# SHIELD_PICO_PTH.net
KiCad netlist of a schematic drawn in EAGLE
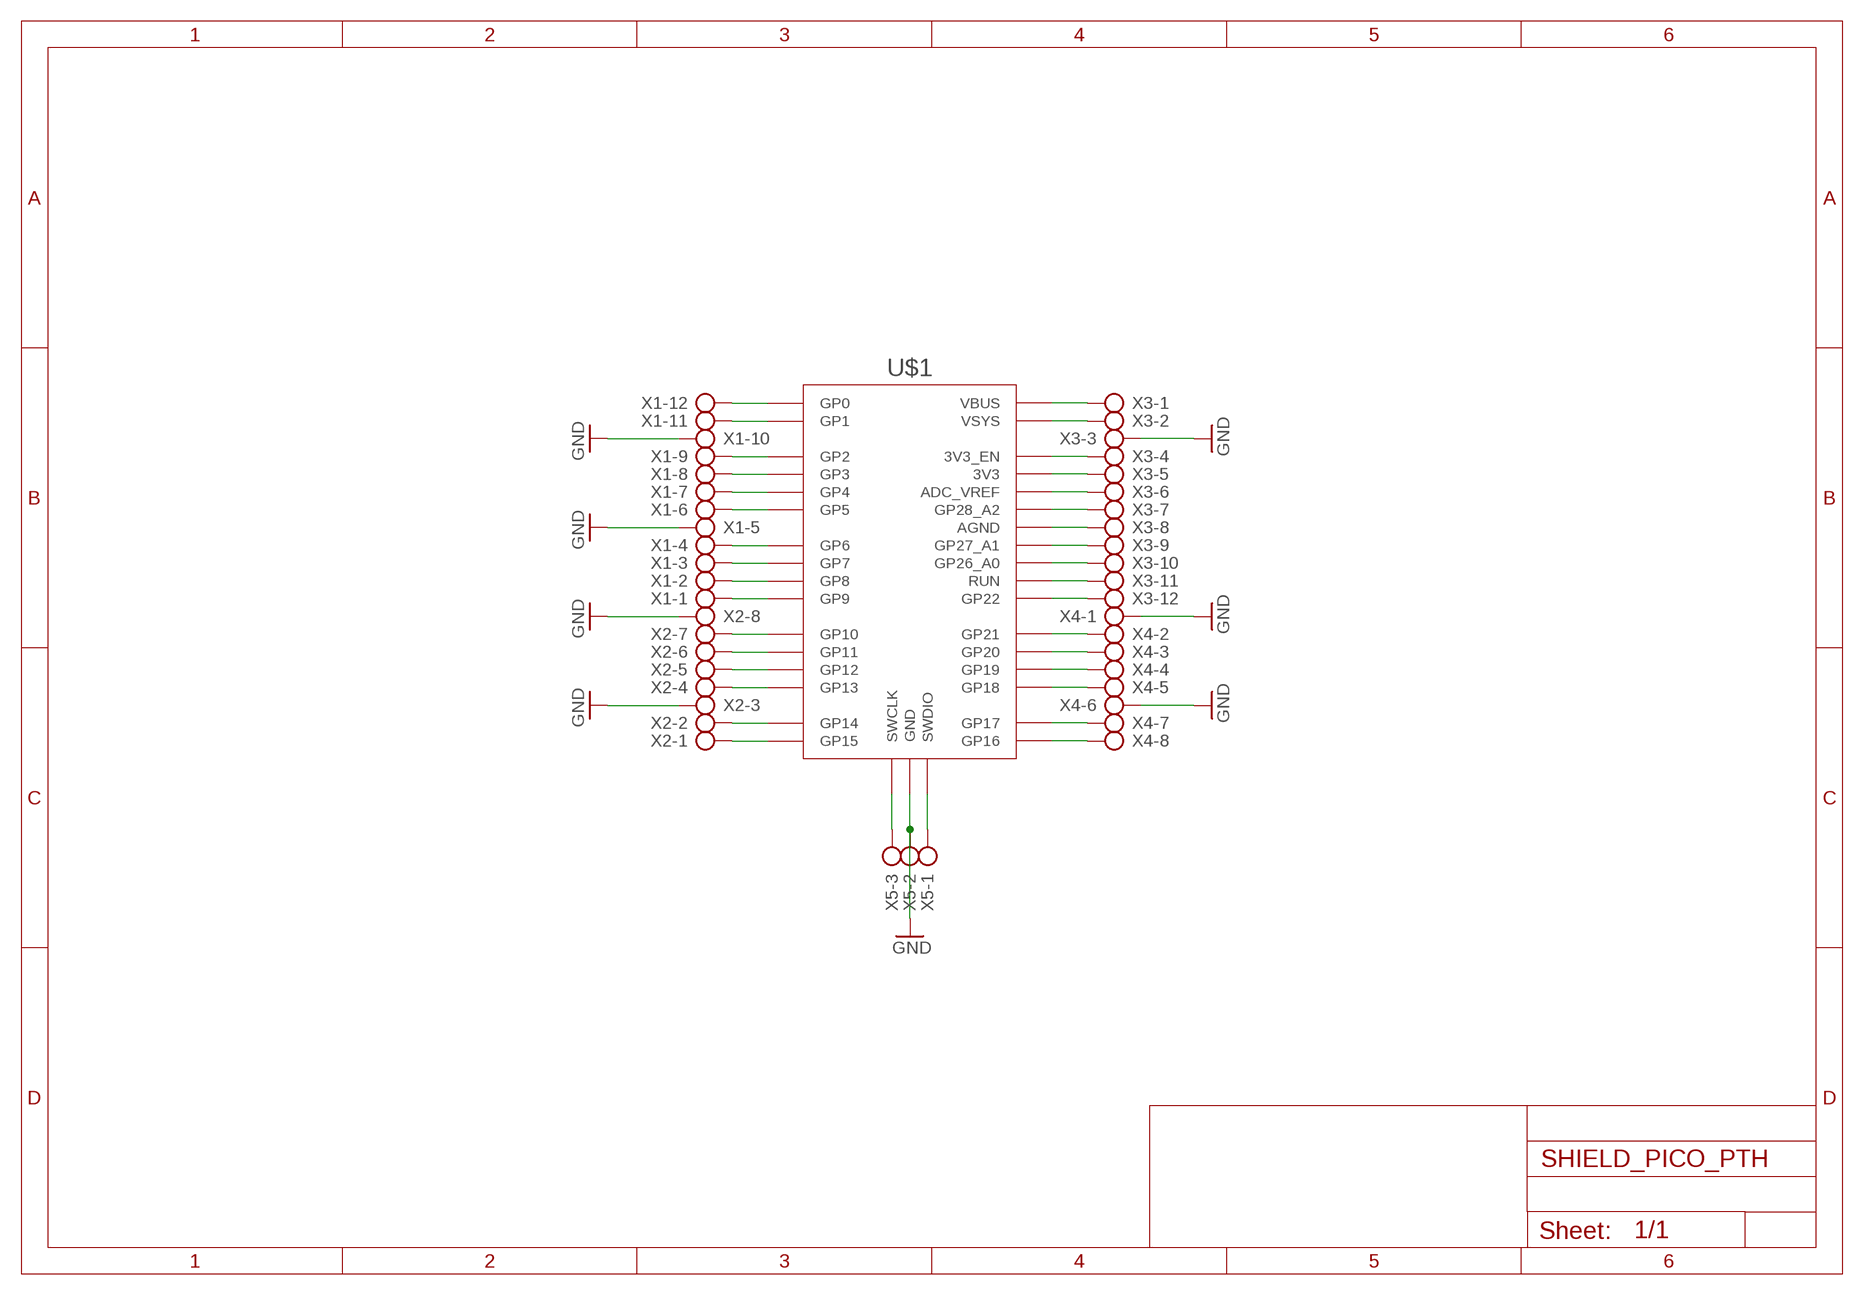
[diagram p0: schematic, sheet 1]

(export (version "E")
  (design (tool "Eeschema 10.0.6"))
  (components
    (comp (ref "U$1")
      (value "RPI_PICO-TH")
      (footprint "eagle-import:RPI_PICO_TH")
      (libsource (lib "eagle-import") (part "RPI_PICO-TH"))
    )
    (comp (ref "X1")
      (value "AK300/12")
      (footprint "eagle-import:AK300_12")
      (libsource (lib "eagle-import") (part "AK300/12"))
    )
    (comp (ref "X2")
      (value "AK300/8")
      (footprint "eagle-import:AK300_8")
      (libsource (lib "eagle-import") (part "AK300/8"))
    )
    (comp (ref "X3")
      (value "AK300/12")
      (footprint "eagle-import:AK300_12")
      (libsource (lib "eagle-import") (part "AK300/12"))
    )
    (comp (ref "X4")
      (value "AK300/8")
      (footprint "eagle-import:AK300_8")
      (libsource (lib "eagle-import") (part "AK300/8"))
    )
    (comp (ref "X5")
      (value "AK300/3")
      (footprint "eagle-import:AK300_3")
      (libsource (lib "eagle-import") (part "AK300/3"))
    )
  )
  (nets
    (net (code "1") (name "GND") (class "Default")
      (node (ref "U$1") (pin "GND@1") (pinfunction "GND_GND@1") (pintype "bidirectional"))
      (node (ref "U$1") (pin "GND@2") (pinfunction "GND_GND@2") (pintype "bidirectional"))
      (node (ref "U$1") (pin "GND@3") (pinfunction "GND_GND@3") (pintype "bidirectional"))
      (node (ref "U$1") (pin "GND@4") (pinfunction "GND_GND@4") (pintype "bidirectional"))
      (node (ref "U$1") (pin "GND@5") (pinfunction "GND_GND@5") (pintype "bidirectional"))
      (node (ref "U$1") (pin "GND@6") (pinfunction "GND_GND@6") (pintype "bidirectional"))
      (node (ref "U$1") (pin "GND@7") (pinfunction "GND_GND@7") (pintype "bidirectional"))
      (node (ref "U$1") (pin "GND@8") (pinfunction "GND_GND@8") (pintype "bidirectional"))
      (node (ref "X1") (pin "10") (pinfunction "KL_10") (pintype "passive"))
      (node (ref "X1") (pin "5") (pinfunction "KL_5") (pintype "passive"))
      (node (ref "X2") (pin "3") (pinfunction "KL_3") (pintype "passive"))
      (node (ref "X2") (pin "8") (pinfunction "KL_8") (pintype "passive"))
      (node (ref "X3") (pin "3") (pinfunction "KL_3") (pintype "passive"))
      (node (ref "X4") (pin "1") (pinfunction "KL_1") (pintype "passive"))
      (node (ref "X4") (pin "6") (pinfunction "KL_6") (pintype "passive"))
      (node (ref "X5") (pin "2") (pinfunction "KL_2") (pintype "passive"))
    )
    (net (code "2") (name "Net-(X1A-KL)") (class "Default")
      (node (ref "U$1") (pin "GP9") (pinfunction "GP9_GP9") (pintype "bidirectional"))
      (node (ref "X1") (pin "1") (pinfunction "KL_1") (pintype "passive"))
    )
    (net (code "3") (name "Net-(X1C-KL)") (class "Default")
      (node (ref "U$1") (pin "GP1") (pinfunction "GP1_GP1") (pintype "bidirectional"))
      (node (ref "X1") (pin "11") (pinfunction "KL_11") (pintype "passive"))
    )
    (net (code "4") (name "Net-(X1D-KL)") (class "Default")
      (node (ref "U$1") (pin "GP0") (pinfunction "GP0_GP0") (pintype "bidirectional"))
      (node (ref "X1") (pin "12") (pinfunction "KL_12") (pintype "passive"))
    )
    (net (code "5") (name "Net-(X1E-KL)") (class "Default")
      (node (ref "U$1") (pin "GP8") (pinfunction "GP8_GP8") (pintype "bidirectional"))
      (node (ref "X1") (pin "2") (pinfunction "KL_2") (pintype "passive"))
    )
    (net (code "6") (name "Net-(X1F-KL)") (class "Default")
      (node (ref "U$1") (pin "GP7") (pinfunction "GP7_GP7") (pintype "bidirectional"))
      (node (ref "X1") (pin "3") (pinfunction "KL_3") (pintype "passive"))
    )
    (net (code "7") (name "Net-(X1G-KL)") (class "Default")
      (node (ref "U$1") (pin "GP6") (pinfunction "GP6_GP6") (pintype "bidirectional"))
      (node (ref "X1") (pin "4") (pinfunction "KL_4") (pintype "passive"))
    )
    (net (code "8") (name "Net-(X1I-KL)") (class "Default")
      (node (ref "U$1") (pin "GP5") (pinfunction "GP5_GP5") (pintype "bidirectional"))
      (node (ref "X1") (pin "6") (pinfunction "KL_6") (pintype "passive"))
    )
    (net (code "9") (name "Net-(X1J-KL)") (class "Default")
      (node (ref "U$1") (pin "GP4") (pinfunction "GP4_GP4") (pintype "bidirectional"))
      (node (ref "X1") (pin "7") (pinfunction "KL_7") (pintype "passive"))
    )
    (net (code "10") (name "Net-(X1K-KL)") (class "Default")
      (node (ref "U$1") (pin "GP3") (pinfunction "GP3_GP3") (pintype "bidirectional"))
      (node (ref "X1") (pin "8") (pinfunction "KL_8") (pintype "passive"))
    )
    (net (code "11") (name "Net-(X1L-KL)") (class "Default")
      (node (ref "U$1") (pin "GP2") (pinfunction "GP2_GP2") (pintype "bidirectional"))
      (node (ref "X1") (pin "9") (pinfunction "KL_9") (pintype "passive"))
    )
    (net (code "12") (name "Net-(X2A-KL)") (class "Default")
      (node (ref "U$1") (pin "GP15") (pinfunction "GP15_GP15") (pintype "bidirectional"))
      (node (ref "X2") (pin "1") (pinfunction "KL_1") (pintype "passive"))
    )
    (net (code "13") (name "Net-(X2B-KL)") (class "Default")
      (node (ref "U$1") (pin "GP14") (pinfunction "GP14_GP14") (pintype "bidirectional"))
      (node (ref "X2") (pin "2") (pinfunction "KL_2") (pintype "passive"))
    )
    (net (code "14") (name "Net-(X2D-KL)") (class "Default")
      (node (ref "U$1") (pin "GP13") (pinfunction "GP13_GP13") (pintype "bidirectional"))
      (node (ref "X2") (pin "4") (pinfunction "KL_4") (pintype "passive"))
    )
    (net (code "15") (name "Net-(X2E-KL)") (class "Default")
      (node (ref "U$1") (pin "GP12") (pinfunction "GP12_GP12") (pintype "bidirectional"))
      (node (ref "X2") (pin "5") (pinfunction "KL_5") (pintype "passive"))
    )
    (net (code "16") (name "Net-(X2F-KL)") (class "Default")
      (node (ref "U$1") (pin "GP11") (pinfunction "GP11_GP11") (pintype "bidirectional"))
      (node (ref "X2") (pin "6") (pinfunction "KL_6") (pintype "passive"))
    )
    (net (code "17") (name "Net-(X2G-KL)") (class "Default")
      (node (ref "U$1") (pin "GP10") (pinfunction "GP10_GP10") (pintype "bidirectional"))
      (node (ref "X2") (pin "7") (pinfunction "KL_7") (pintype "passive"))
    )
    (net (code "18") (name "Net-(X3A-KL)") (class "Default")
      (node (ref "U$1") (pin "VBUS") (pinfunction "VBUS_VBUS") (pintype "bidirectional"))
      (node (ref "X3") (pin "1") (pinfunction "KL_1") (pintype "passive"))
    )
    (net (code "19") (name "Net-(X3B-KL)") (class "Default")
      (node (ref "U$1") (pin "GP26_A0") (pinfunction "GP26_A0_GP26_A0") (pintype "bidirectional"))
      (node (ref "X3") (pin "10") (pinfunction "KL_10") (pintype "passive"))
    )
    (net (code "20") (name "Net-(X3C-KL)") (class "Default")
      (node (ref "U$1") (pin "RUN") (pinfunction "RUN_RUN") (pintype "bidirectional"))
      (node (ref "X3") (pin "11") (pinfunction "KL_11") (pintype "passive"))
    )
    (net (code "21") (name "Net-(X3D-KL)") (class "Default")
      (node (ref "U$1") (pin "GP22") (pinfunction "GP22_GP22") (pintype "bidirectional"))
      (node (ref "X3") (pin "12") (pinfunction "KL_12") (pintype "passive"))
    )
    (net (code "22") (name "Net-(X3E-KL)") (class "Default")
      (node (ref "U$1") (pin "VSYS") (pinfunction "VSYS_VSYS") (pintype "bidirectional"))
      (node (ref "X3") (pin "2") (pinfunction "KL_2") (pintype "passive"))
    )
    (net (code "23") (name "Net-(X3G-KL)") (class "Default")
      (node (ref "U$1") (pin "3V3_EN") (pinfunction "3V3_EN_3V3_EN") (pintype "bidirectional"))
      (node (ref "X3") (pin "4") (pinfunction "KL_4") (pintype "passive"))
    )
    (net (code "24") (name "Net-(X3H-KL)") (class "Default")
      (node (ref "U$1") (pin "3V3") (pinfunction "3V3_3V3") (pintype "bidirectional"))
      (node (ref "X3") (pin "5") (pinfunction "KL_5") (pintype "passive"))
    )
    (net (code "25") (name "Net-(X3I-KL)") (class "Default")
      (node (ref "U$1") (pin "ADC_VREF") (pinfunction "ADC_VREF_ADC_VREF") (pintype "bidirectional"))
      (node (ref "X3") (pin "6") (pinfunction "KL_6") (pintype "passive"))
    )
    (net (code "26") (name "Net-(X3J-KL)") (class "Default")
      (node (ref "U$1") (pin "GP28_A2") (pinfunction "GP28_A2_GP28_A2") (pintype "bidirectional"))
      (node (ref "X3") (pin "7") (pinfunction "KL_7") (pintype "passive"))
    )
    (net (code "27") (name "Net-(X3K-KL)") (class "Default")
      (node (ref "U$1") (pin "AGND") (pinfunction "AGND_AGND") (pintype "bidirectional"))
      (node (ref "X3") (pin "8") (pinfunction "KL_8") (pintype "passive"))
    )
    (net (code "28") (name "Net-(X3L-KL)") (class "Default")
      (node (ref "U$1") (pin "GP27_A1") (pinfunction "GP27_A1_GP27_A1") (pintype "bidirectional"))
      (node (ref "X3") (pin "9") (pinfunction "KL_9") (pintype "passive"))
    )
    (net (code "29") (name "Net-(X4B-KL)") (class "Default")
      (node (ref "U$1") (pin "GP21") (pinfunction "GP21_GP21") (pintype "bidirectional"))
      (node (ref "X4") (pin "2") (pinfunction "KL_2") (pintype "passive"))
    )
    (net (code "30") (name "Net-(X4C-KL)") (class "Default")
      (node (ref "U$1") (pin "GP20") (pinfunction "GP20_GP20") (pintype "bidirectional"))
      (node (ref "X4") (pin "3") (pinfunction "KL_3") (pintype "passive"))
    )
    (net (code "31") (name "Net-(X4D-KL)") (class "Default")
      (node (ref "U$1") (pin "GP19") (pinfunction "GP19_GP19") (pintype "bidirectional"))
      (node (ref "X4") (pin "4") (pinfunction "KL_4") (pintype "passive"))
    )
    (net (code "32") (name "Net-(X4E-KL)") (class "Default")
      (node (ref "U$1") (pin "GP18") (pinfunction "GP18_GP18") (pintype "bidirectional"))
      (node (ref "X4") (pin "5") (pinfunction "KL_5") (pintype "passive"))
    )
    (net (code "33") (name "Net-(X4G-KL)") (class "Default")
      (node (ref "U$1") (pin "GP17") (pinfunction "GP17_GP17") (pintype "bidirectional"))
      (node (ref "X4") (pin "7") (pinfunction "KL_7") (pintype "passive"))
    )
    (net (code "34") (name "Net-(X4H-KL)") (class "Default")
      (node (ref "U$1") (pin "GP16") (pinfunction "GP16_GP16") (pintype "bidirectional"))
      (node (ref "X4") (pin "8") (pinfunction "KL_8") (pintype "passive"))
    )
    (net (code "35") (name "Net-(X5A-KL)") (class "Default")
      (node (ref "U$1") (pin "SWDIO") (pinfunction "SWDIO_SWDIO") (pintype "bidirectional"))
      (node (ref "X5") (pin "1") (pinfunction "KL_1") (pintype "passive"))
    )
    (net (code "36") (name "Net-(X5C-KL)") (class "Default")
      (node (ref "U$1") (pin "SWCLK") (pinfunction "SWCLK_SWCLK") (pintype "bidirectional"))
      (node (ref "X5") (pin "3") (pinfunction "KL_3") (pintype "passive"))
    )
  )
)
